# filter.net
KiCad netlist of a schematic drawn in Altium Designer
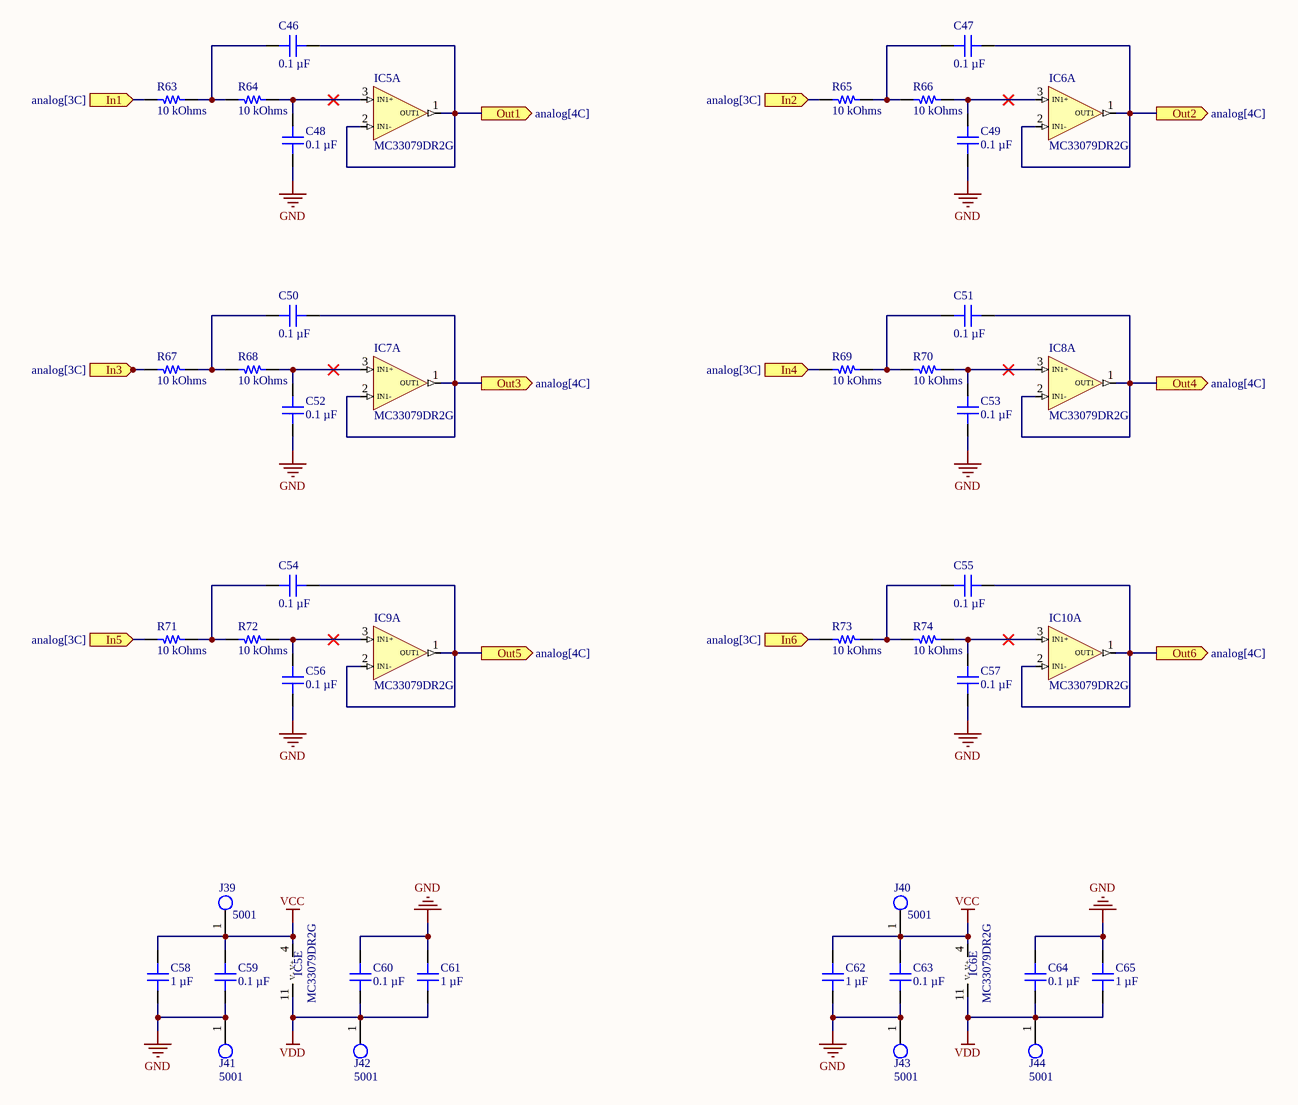
[diagram p0: filter.SchDoc]

(export (version "E")
  (design (tool "Eeschema 10.0.6"))
  (components
    (comp (ref "C46")
      (value "0.1 µF")
      (footprint "CAP 1206_3216 - 0.8MM")
      (description "CAP CER 0.1UF 50V X7R 1206")
      (fields
        (field (name "PART NUMBER") "885012208087")
        (field (name "CAPACITANCE") "0.1 µF")
        (field (name "MANUFACTURER") "Würth Elektronik")
      )
      (libsource (lib "Celestial Altium Library - altium_library") (part "Capacitor"))
    )
    (comp (ref "C47")
      (value "0.1 µF")
      (footprint "CAP 1206_3216 - 0.8MM")
      (description "CAP CER 0.1UF 50V X7R 1206")
      (fields
        (field (name "PART NUMBER") "885012208087")
        (field (name "CAPACITANCE") "0.1 µF")
        (field (name "MANUFACTURER") "Würth Elektronik")
      )
      (libsource (lib "Celestial Altium Library - altium_library") (part "Capacitor"))
    )
    (comp (ref "C48")
      (value "0.1 µF")
      (footprint "CAP 1206_3216 - 0.8MM")
      (description "CAP CER 0.1UF 50V X7R 1206")
      (fields
        (field (name "PART NUMBER") "885012208087")
        (field (name "CAPACITANCE") "0.1 µF")
        (field (name "MANUFACTURER") "Würth Elektronik")
      )
      (libsource (lib "Celestial Altium Library - altium_library") (part "Capacitor"))
    )
    (comp (ref "C49")
      (value "0.1 µF")
      (footprint "CAP 1206_3216 - 0.8MM")
      (description "CAP CER 0.1UF 50V X7R 1206")
      (fields
        (field (name "PART NUMBER") "885012208087")
        (field (name "CAPACITANCE") "0.1 µF")
        (field (name "MANUFACTURER") "Würth Elektronik")
      )
      (libsource (lib "Celestial Altium Library - altium_library") (part "Capacitor"))
    )
    (comp (ref "C50")
      (value "0.1 µF")
      (footprint "CAP 1206_3216 - 0.8MM")
      (description "CAP CER 0.1UF 50V X7R 1206")
      (fields
        (field (name "PART NUMBER") "885012208087")
        (field (name "CAPACITANCE") "0.1 µF")
        (field (name "MANUFACTURER") "Würth Elektronik")
      )
      (libsource (lib "Celestial Altium Library - altium_library") (part "Capacitor"))
    )
    (comp (ref "C51")
      (value "0.1 µF")
      (footprint "CAP 1206_3216 - 0.8MM")
      (description "CAP CER 0.1UF 50V X7R 1206")
      (fields
        (field (name "PART NUMBER") "885012208087")
        (field (name "CAPACITANCE") "0.1 µF")
        (field (name "MANUFACTURER") "Würth Elektronik")
      )
      (libsource (lib "Celestial Altium Library - altium_library") (part "Capacitor"))
    )
    (comp (ref "C52")
      (value "0.1 µF")
      (footprint "CAP 1206_3216 - 0.8MM")
      (description "CAP CER 0.1UF 50V X7R 1206")
      (fields
        (field (name "PART NUMBER") "885012208087")
        (field (name "CAPACITANCE") "0.1 µF")
        (field (name "MANUFACTURER") "Würth Elektronik")
      )
      (libsource (lib "Celestial Altium Library - altium_library") (part "Capacitor"))
    )
    (comp (ref "C53")
      (value "0.1 µF")
      (footprint "CAP 1206_3216 - 0.8MM")
      (description "CAP CER 0.1UF 50V X7R 1206")
      (fields
        (field (name "PART NUMBER") "885012208087")
        (field (name "CAPACITANCE") "0.1 µF")
        (field (name "MANUFACTURER") "Würth Elektronik")
      )
      (libsource (lib "Celestial Altium Library - altium_library") (part "Capacitor"))
    )
    (comp (ref "C54")
      (value "0.1 µF")
      (footprint "CAP 1206_3216 - 0.8MM")
      (description "CAP CER 0.1UF 50V X7R 1206")
      (fields
        (field (name "PART NUMBER") "885012208087")
        (field (name "CAPACITANCE") "0.1 µF")
        (field (name "MANUFACTURER") "Würth Elektronik")
      )
      (libsource (lib "Celestial Altium Library - altium_library") (part "Capacitor"))
    )
    (comp (ref "C55")
      (value "0.1 µF")
      (footprint "CAP 1206_3216 - 0.8MM")
      (description "CAP CER 0.1UF 50V X7R 1206")
      (fields
        (field (name "PART NUMBER") "885012208087")
        (field (name "CAPACITANCE") "0.1 µF")
        (field (name "MANUFACTURER") "Würth Elektronik")
      )
      (libsource (lib "Celestial Altium Library - altium_library") (part "Capacitor"))
    )
    (comp (ref "C56")
      (value "0.1 µF")
      (footprint "CAP 1206_3216 - 0.8MM")
      (description "CAP CER 0.1UF 50V X7R 1206")
      (fields
        (field (name "PART NUMBER") "885012208087")
        (field (name "CAPACITANCE") "0.1 µF")
        (field (name "MANUFACTURER") "Würth Elektronik")
      )
      (libsource (lib "Celestial Altium Library - altium_library") (part "Capacitor"))
    )
    (comp (ref "C57")
      (value "0.1 µF")
      (footprint "CAP 1206_3216 - 0.8MM")
      (description "CAP CER 0.1UF 50V X7R 1206")
      (fields
        (field (name "PART NUMBER") "885012208087")
        (field (name "CAPACITANCE") "0.1 µF")
        (field (name "MANUFACTURER") "Würth Elektronik")
      )
      (libsource (lib "Celestial Altium Library - altium_library") (part "Capacitor"))
    )
    (comp (ref "C58")
      (value "1 µF")
      (footprint "CAP 1206_3216 - 0.8MM")
      (description "CAP CER 1UF 50V X7R 1206")
      (fields
        (field (name "PART NUMBER") "885012208093")
        (field (name "CAPACITANCE") "1 µF")
        (field (name "MANUFACTURER") "Würth Elektronik")
      )
      (libsource (lib "Celestial Altium Library - altium_library") (part "Capacitor"))
    )
    (comp (ref "C59")
      (value "0.1 µF")
      (footprint "CAP 1206_3216 - 0.8MM")
      (description "CAP CER 0.1UF 50V X7R 1206")
      (fields
        (field (name "PART NUMBER") "885012208087")
        (field (name "CAPACITANCE") "0.1 µF")
        (field (name "MANUFACTURER") "Würth Elektronik")
      )
      (libsource (lib "Celestial Altium Library - altium_library") (part "Capacitor"))
    )
    (comp (ref "C60")
      (value "0.1 µF")
      (footprint "CAP 1206_3216 - 0.8MM")
      (description "CAP CER 0.1UF 50V X7R 1206")
      (fields
        (field (name "PART NUMBER") "885012208087")
        (field (name "CAPACITANCE") "0.1 µF")
        (field (name "MANUFACTURER") "Würth Elektronik")
      )
      (libsource (lib "Celestial Altium Library - altium_library") (part "Capacitor"))
    )
    (comp (ref "C61")
      (value "1 µF")
      (footprint "CAP 1206_3216 - 0.8MM")
      (description "CAP CER 1UF 50V X7R 1206")
      (fields
        (field (name "PART NUMBER") "885012208093")
        (field (name "CAPACITANCE") "1 µF")
        (field (name "MANUFACTURER") "Würth Elektronik")
      )
      (libsource (lib "Celestial Altium Library - altium_library") (part "Capacitor"))
    )
    (comp (ref "C62")
      (value "1 µF")
      (footprint "CAP 1206_3216 - 0.8MM")
      (description "CAP CER 1UF 50V X7R 1206")
      (fields
        (field (name "PART NUMBER") "885012208093")
        (field (name "CAPACITANCE") "1 µF")
        (field (name "MANUFACTURER") "Würth Elektronik")
      )
      (libsource (lib "Celestial Altium Library - altium_library") (part "Capacitor"))
    )
    (comp (ref "C63")
      (value "0.1 µF")
      (footprint "CAP 1206_3216 - 0.8MM")
      (description "CAP CER 0.1UF 50V X7R 1206")
      (fields
        (field (name "PART NUMBER") "885012208087")
        (field (name "CAPACITANCE") "0.1 µF")
        (field (name "MANUFACTURER") "Würth Elektronik")
      )
      (libsource (lib "Celestial Altium Library - altium_library") (part "Capacitor"))
    )
    (comp (ref "C64")
      (value "0.1 µF")
      (footprint "CAP 1206_3216 - 0.8MM")
      (description "CAP CER 0.1UF 50V X7R 1206")
      (fields
        (field (name "PART NUMBER") "885012208087")
        (field (name "CAPACITANCE") "0.1 µF")
        (field (name "MANUFACTURER") "Würth Elektronik")
      )
      (libsource (lib "Celestial Altium Library - altium_library") (part "Capacitor"))
    )
    (comp (ref "C65")
      (value "1 µF")
      (footprint "CAP 1206_3216 - 0.8MM")
      (description "CAP CER 1UF 50V X7R 1206")
      (fields
        (field (name "PART NUMBER") "885012208093")
        (field (name "CAPACITANCE") "1 µF")
        (field (name "MANUFACTURER") "Würth Elektronik")
      )
      (libsource (lib "Celestial Altium Library - altium_library") (part "Capacitor"))
    )
    (comp (ref "IC5")
      (value "MC33079DR2G")
      (footprint "SOIC127P600X175-14N")
      (description "Integrated Circuit")
      (fields (field (name "MOUSER PART NUMBER") "863-MC33079DR2G"))
      (libsource (lib "za_koncar") (part "MC33079DR2G"))
    )
    (comp (ref "IC6")
      (value "MC33079DR2G")
      (footprint "SOIC127P600X175-14N")
      (description "Integrated Circuit")
      (fields (field (name "MOUSER PART NUMBER") "863-MC33079DR2G"))
      (libsource (lib "za_koncar") (part "MC33079DR2G"))
    )
    (comp (ref "IC7")
      (value "MC33079DR2G")
      (footprint "SOIC127P600X175-14N")
      (description "Integrated Circuit")
      (fields (field (name "MOUSER PART NUMBER") "863-MC33079DR2G"))
      (libsource (lib "za_koncar") (part "MC33079DR2G"))
    )
    (comp (ref "IC8")
      (value "MC33079DR2G")
      (footprint "SOIC127P600X175-14N")
      (description "Integrated Circuit")
      (fields (field (name "MOUSER PART NUMBER") "863-MC33079DR2G"))
      (libsource (lib "za_koncar") (part "MC33079DR2G"))
    )
    (comp (ref "IC9")
      (value "MC33079DR2G")
      (footprint "SOIC127P600X175-14N")
      (description "Integrated Circuit")
      (fields (field (name "MOUSER PART NUMBER") "863-MC33079DR2G"))
      (libsource (lib "za_koncar") (part "MC33079DR2G"))
    )
    (comp (ref "IC10")
      (value "MC33079DR2G")
      (footprint "SOIC127P600X175-14N")
      (description "Integrated Circuit")
      (fields (field (name "MOUSER PART NUMBER") "863-MC33079DR2G"))
      (libsource (lib "za_koncar") (part "MC33079DR2G"))
    )
    (comp (ref "J39")
      (value "5001")
      (footprint "FP-5001-MFG")
      (description "PC TEST POINT MINIATURE BLACK")
      (libsource (lib "za_koncar") (part "CMP-2000-05181-2"))
    )
    (comp (ref "J40")
      (value "5001")
      (footprint "FP-5001-MFG")
      (description "PC TEST POINT MINIATURE BLACK")
      (libsource (lib "za_koncar") (part "CMP-2000-05181-2"))
    )
    (comp (ref "J41")
      (value "5001")
      (footprint "FP-5001-MFG")
      (description "PC TEST POINT MINIATURE BLACK")
      (libsource (lib "za_koncar") (part "CMP-2000-05181-2"))
    )
    (comp (ref "J42")
      (value "5001")
      (footprint "FP-5001-MFG")
      (description "PC TEST POINT MINIATURE BLACK")
      (libsource (lib "za_koncar") (part "CMP-2000-05181-2"))
    )
    (comp (ref "J43")
      (value "5001")
      (footprint "FP-5001-MFG")
      (description "PC TEST POINT MINIATURE BLACK")
      (libsource (lib "za_koncar") (part "CMP-2000-05181-2"))
    )
    (comp (ref "J44")
      (value "5001")
      (footprint "FP-5001-MFG")
      (description "PC TEST POINT MINIATURE BLACK")
      (libsource (lib "za_koncar") (part "CMP-2000-05181-2"))
    )
    (comp (ref "R63")
      (value "10 kOhms")
      (footprint "YAGEO RES 1206_3216")
      (description "RES SMD 10K OHM 1% 1/4W 1206")
      (fields (field (name "PART NUMBER") "RT1206FRE0710KL") (field (name "MANUFACTURER") "Yageo"))
      (libsource (lib "Celestial Altium Library - altium_library") (part "Resistor"))
    )
    (comp (ref "R64")
      (value "10 kOhms")
      (footprint "YAGEO RES 1206_3216")
      (description "RES SMD 10K OHM 1% 1/4W 1206")
      (fields (field (name "PART NUMBER") "RT1206FRE0710KL") (field (name "MANUFACTURER") "Yageo"))
      (libsource (lib "Celestial Altium Library - altium_library") (part "Resistor"))
    )
    (comp (ref "R65")
      (value "10 kOhms")
      (footprint "YAGEO RES 1206_3216")
      (description "RES SMD 10K OHM 1% 1/4W 1206")
      (fields (field (name "PART NUMBER") "RT1206FRE0710KL") (field (name "MANUFACTURER") "Yageo"))
      (libsource (lib "Celestial Altium Library - altium_library") (part "Resistor"))
    )
    (comp (ref "R66")
      (value "10 kOhms")
      (footprint "YAGEO RES 1206_3216")
      (description "RES SMD 10K OHM 1% 1/4W 1206")
      (fields (field (name "PART NUMBER") "RT1206FRE0710KL") (field (name "MANUFACTURER") "Yageo"))
      (libsource (lib "Celestial Altium Library - altium_library") (part "Resistor"))
    )
    (comp (ref "R67")
      (value "10 kOhms")
      (footprint "YAGEO RES 1206_3216")
      (description "RES SMD 10K OHM 1% 1/4W 1206")
      (fields (field (name "PART NUMBER") "RT1206FRE0710KL") (field (name "MANUFACTURER") "Yageo"))
      (libsource (lib "Celestial Altium Library - altium_library") (part "Resistor"))
    )
    (comp (ref "R68")
      (value "10 kOhms")
      (footprint "YAGEO RES 1206_3216")
      (description "RES SMD 10K OHM 1% 1/4W 1206")
      (fields (field (name "PART NUMBER") "RT1206FRE0710KL") (field (name "MANUFACTURER") "Yageo"))
      (libsource (lib "Celestial Altium Library - altium_library") (part "Resistor"))
    )
    (comp (ref "R69")
      (value "10 kOhms")
      (footprint "YAGEO RES 1206_3216")
      (description "RES SMD 10K OHM 1% 1/4W 1206")
      (fields (field (name "PART NUMBER") "RT1206FRE0710KL") (field (name "MANUFACTURER") "Yageo"))
      (libsource (lib "Celestial Altium Library - altium_library") (part "Resistor"))
    )
    (comp (ref "R70")
      (value "10 kOhms")
      (footprint "YAGEO RES 1206_3216")
      (description "RES SMD 10K OHM 1% 1/4W 1206")
      (fields (field (name "PART NUMBER") "RT1206FRE0710KL") (field (name "MANUFACTURER") "Yageo"))
      (libsource (lib "Celestial Altium Library - altium_library") (part "Resistor"))
    )
    (comp (ref "R71")
      (value "10 kOhms")
      (footprint "YAGEO RES 1206_3216")
      (description "RES SMD 10K OHM 1% 1/4W 1206")
      (fields (field (name "PART NUMBER") "RT1206FRE0710KL") (field (name "MANUFACTURER") "Yageo"))
      (libsource (lib "Celestial Altium Library - altium_library") (part "Resistor"))
    )
    (comp (ref "R72")
      (value "10 kOhms")
      (footprint "YAGEO RES 1206_3216")
      (description "RES SMD 10K OHM 1% 1/4W 1206")
      (fields (field (name "PART NUMBER") "RT1206FRE0710KL") (field (name "MANUFACTURER") "Yageo"))
      (libsource (lib "Celestial Altium Library - altium_library") (part "Resistor"))
    )
    (comp (ref "R73")
      (value "10 kOhms")
      (footprint "YAGEO RES 1206_3216")
      (description "RES SMD 10K OHM 1% 1/4W 1206")
      (fields (field (name "PART NUMBER") "RT1206FRE0710KL") (field (name "MANUFACTURER") "Yageo"))
      (libsource (lib "Celestial Altium Library - altium_library") (part "Resistor"))
    )
    (comp (ref "R74")
      (value "10 kOhms")
      (footprint "YAGEO RES 1206_3216")
      (description "RES SMD 10K OHM 1% 1/4W 1206")
      (fields (field (name "PART NUMBER") "RT1206FRE0710KL") (field (name "MANUFACTURER") "Yageo"))
      (libsource (lib "Celestial Altium Library - altium_library") (part "Resistor"))
    )
  )
  (nets
    (net (code "1") (name "/In1") (class "Default")
      (node (ref "R63") (pin "2") (pinfunction "2_2") (pintype "passive"))
    )
    (net (code "2") (name "/In2") (class "Default")
      (node (ref "R65") (pin "2") (pinfunction "2_2") (pintype "passive"))
    )
    (net (code "3") (name "/In3") (class "Default")
      (node (ref "R67") (pin "2") (pinfunction "2_2") (pintype "passive"))
    )
    (net (code "4") (name "/In4") (class "Default")
      (node (ref "R69") (pin "2") (pinfunction "2_2") (pintype "passive"))
    )
    (net (code "5") (name "/In5") (class "Default")
      (node (ref "R71") (pin "2") (pinfunction "2_2") (pintype "passive"))
    )
    (net (code "6") (name "/In6") (class "Default")
      (node (ref "R73") (pin "2") (pinfunction "2_2") (pintype "passive"))
    )
    (net (code "7") (name "/Out1") (class "Default")
      (node (ref "C46") (pin "1") (pinfunction "1_1") (pintype "passive"))
      (node (ref "IC5") (pin "1") (pinfunction "OUT1_1") (pintype "output"))
      (node (ref "IC5") (pin "2") (pinfunction "IN1-_2") (pintype "input"))
    )
    (net (code "8") (name "/Out2") (class "Default")
      (node (ref "C47") (pin "1") (pinfunction "1_1") (pintype "passive"))
      (node (ref "IC6") (pin "1") (pinfunction "OUT1_1") (pintype "output"))
      (node (ref "IC6") (pin "2") (pinfunction "IN1-_2") (pintype "input"))
    )
    (net (code "9") (name "/Out3") (class "Default")
      (node (ref "C50") (pin "1") (pinfunction "1_1") (pintype "passive"))
      (node (ref "IC7") (pin "1") (pinfunction "OUT1_1") (pintype "output"))
      (node (ref "IC7") (pin "2") (pinfunction "IN1-_2") (pintype "input"))
    )
    (net (code "10") (name "/Out4") (class "Default")
      (node (ref "C51") (pin "1") (pinfunction "1_1") (pintype "passive"))
      (node (ref "IC8") (pin "1") (pinfunction "OUT1_1") (pintype "output"))
      (node (ref "IC8") (pin "2") (pinfunction "IN1-_2") (pintype "input"))
    )
    (net (code "11") (name "/Out5") (class "Default")
      (node (ref "C54") (pin "1") (pinfunction "1_1") (pintype "passive"))
      (node (ref "IC9") (pin "1") (pinfunction "OUT1_1") (pintype "output"))
      (node (ref "IC9") (pin "2") (pinfunction "IN1-_2") (pintype "input"))
    )
    (net (code "12") (name "/Out6") (class "Default")
      (node (ref "C55") (pin "1") (pinfunction "1_1") (pintype "passive"))
      (node (ref "IC10") (pin "1") (pinfunction "OUT1_1") (pintype "output"))
      (node (ref "IC10") (pin "2") (pinfunction "IN1-_2") (pintype "input"))
    )
    (net (code "13") (name "GND") (class "Default")
      (node (ref "C48") (pin "2") (pinfunction "2_2") (pintype "passive"))
      (node (ref "C49") (pin "2") (pinfunction "2_2") (pintype "passive"))
      (node (ref "C52") (pin "2") (pinfunction "2_2") (pintype "passive"))
      (node (ref "C53") (pin "2") (pinfunction "2_2") (pintype "passive"))
      (node (ref "C56") (pin "2") (pinfunction "2_2") (pintype "passive"))
      (node (ref "C57") (pin "2") (pinfunction "2_2") (pintype "passive"))
      (node (ref "C58") (pin "1") (pinfunction "1_1") (pintype "passive"))
      (node (ref "C59") (pin "1") (pinfunction "1_1") (pintype "passive"))
      (node (ref "C60") (pin "2") (pinfunction "2_2") (pintype "passive"))
      (node (ref "C61") (pin "2") (pinfunction "2_2") (pintype "passive"))
      (node (ref "C62") (pin "1") (pinfunction "1_1") (pintype "passive"))
      (node (ref "C63") (pin "1") (pinfunction "1_1") (pintype "passive"))
      (node (ref "C64") (pin "2") (pinfunction "2_2") (pintype "passive"))
      (node (ref "C65") (pin "2") (pinfunction "2_2") (pintype "passive"))
      (node (ref "J41") (pin "1") (pinfunction "1_1") (pintype "passive"))
      (node (ref "J43") (pin "1") (pinfunction "1_1") (pintype "passive"))
    )
    (net (code "14") (name "Net-(C46-Pad2)") (class "Default")
      (node (ref "C46") (pin "2") (pinfunction "2_2") (pintype "passive"))
      (node (ref "R63") (pin "1") (pinfunction "1_1") (pintype "passive"))
      (node (ref "R64") (pin "2") (pinfunction "2_2") (pintype "passive"))
    )
    (net (code "15") (name "Net-(C47-Pad2)") (class "Default")
      (node (ref "C47") (pin "2") (pinfunction "2_2") (pintype "passive"))
      (node (ref "R65") (pin "1") (pinfunction "1_1") (pintype "passive"))
      (node (ref "R66") (pin "2") (pinfunction "2_2") (pintype "passive"))
    )
    (net (code "16") (name "Net-(C50-Pad2)") (class "Default")
      (node (ref "C50") (pin "2") (pinfunction "2_2") (pintype "passive"))
      (node (ref "R67") (pin "1") (pinfunction "1_1") (pintype "passive"))
      (node (ref "R68") (pin "2") (pinfunction "2_2") (pintype "passive"))
    )
    (net (code "17") (name "Net-(C51-Pad2)") (class "Default")
      (node (ref "C51") (pin "2") (pinfunction "2_2") (pintype "passive"))
      (node (ref "R69") (pin "1") (pinfunction "1_1") (pintype "passive"))
      (node (ref "R70") (pin "2") (pinfunction "2_2") (pintype "passive"))
    )
    (net (code "18") (name "Net-(C54-Pad2)") (class "Default")
      (node (ref "C54") (pin "2") (pinfunction "2_2") (pintype "passive"))
      (node (ref "R71") (pin "1") (pinfunction "1_1") (pintype "passive"))
      (node (ref "R72") (pin "2") (pinfunction "2_2") (pintype "passive"))
    )
    (net (code "19") (name "Net-(C55-Pad2)") (class "Default")
      (node (ref "C55") (pin "2") (pinfunction "2_2") (pintype "passive"))
      (node (ref "R73") (pin "1") (pinfunction "1_1") (pintype "passive"))
      (node (ref "R74") (pin "2") (pinfunction "2_2") (pintype "passive"))
    )
    (net (code "20") (name "Net-(IC5A-IN1+)") (class "Default")
      (node (ref "C48") (pin "1") (pinfunction "1_1") (pintype "passive"))
      (node (ref "IC5") (pin "3") (pinfunction "IN1+_3") (pintype "input"))
      (node (ref "R64") (pin "1") (pinfunction "1_1") (pintype "passive"))
    )
    (net (code "21") (name "Net-(IC6A-IN1+)") (class "Default")
      (node (ref "C49") (pin "1") (pinfunction "1_1") (pintype "passive"))
      (node (ref "IC6") (pin "3") (pinfunction "IN1+_3") (pintype "input"))
      (node (ref "R66") (pin "1") (pinfunction "1_1") (pintype "passive"))
    )
    (net (code "22") (name "Net-(IC7A-IN1+)") (class "Default")
      (node (ref "C52") (pin "1") (pinfunction "1_1") (pintype "passive"))
      (node (ref "IC7") (pin "3") (pinfunction "IN1+_3") (pintype "input"))
      (node (ref "R68") (pin "1") (pinfunction "1_1") (pintype "passive"))
    )
    (net (code "23") (name "Net-(IC8A-IN1+)") (class "Default")
      (node (ref "C53") (pin "1") (pinfunction "1_1") (pintype "passive"))
      (node (ref "IC8") (pin "3") (pinfunction "IN1+_3") (pintype "input"))
      (node (ref "R70") (pin "1") (pinfunction "1_1") (pintype "passive"))
    )
    (net (code "24") (name "Net-(IC9A-IN1+)") (class "Default")
      (node (ref "C56") (pin "1") (pinfunction "1_1") (pintype "passive"))
      (node (ref "IC9") (pin "3") (pinfunction "IN1+_3") (pintype "input"))
      (node (ref "R72") (pin "1") (pinfunction "1_1") (pintype "passive"))
    )
    (net (code "25") (name "Net-(IC10A-IN1+)") (class "Default")
      (node (ref "C57") (pin "1") (pinfunction "1_1") (pintype "passive"))
      (node (ref "IC10") (pin "3") (pinfunction "IN1+_3") (pintype "input"))
      (node (ref "R74") (pin "1") (pinfunction "1_1") (pintype "passive"))
    )
    (net (code "26") (name "VCC") (class "Default")
      (node (ref "C58") (pin "2") (pinfunction "2_2") (pintype "passive"))
      (node (ref "C59") (pin "2") (pinfunction "2_2") (pintype "passive"))
      (node (ref "C62") (pin "2") (pinfunction "2_2") (pintype "passive"))
      (node (ref "C63") (pin "2") (pinfunction "2_2") (pintype "passive"))
      (node (ref "IC5") (pin "4") (pinfunction "V+_4") (pintype "power_in"))
      (node (ref "IC6") (pin "4") (pinfunction "V+_4") (pintype "power_in"))
      (node (ref "J39") (pin "1") (pinfunction "1_1") (pintype "passive"))
      (node (ref "J40") (pin "1") (pinfunction "1_1") (pintype "passive"))
    )
    (net (code "27") (name "VDD") (class "Default")
      (node (ref "C60") (pin "1") (pinfunction "1_1") (pintype "passive"))
      (node (ref "C61") (pin "1") (pinfunction "1_1") (pintype "passive"))
      (node (ref "C64") (pin "1") (pinfunction "1_1") (pintype "passive"))
      (node (ref "C65") (pin "1") (pinfunction "1_1") (pintype "passive"))
      (node (ref "IC5") (pin "11") (pinfunction "V-_11") (pintype "power_in"))
      (node (ref "IC6") (pin "11") (pinfunction "V-_11") (pintype "power_in"))
      (node (ref "J42") (pin "1") (pinfunction "1_1") (pintype "passive"))
      (node (ref "J44") (pin "1") (pinfunction "1_1") (pintype "passive"))
    )
  )
)
